# untitled_3.net
KiCad netlist of a schematic drawn in EAGLE
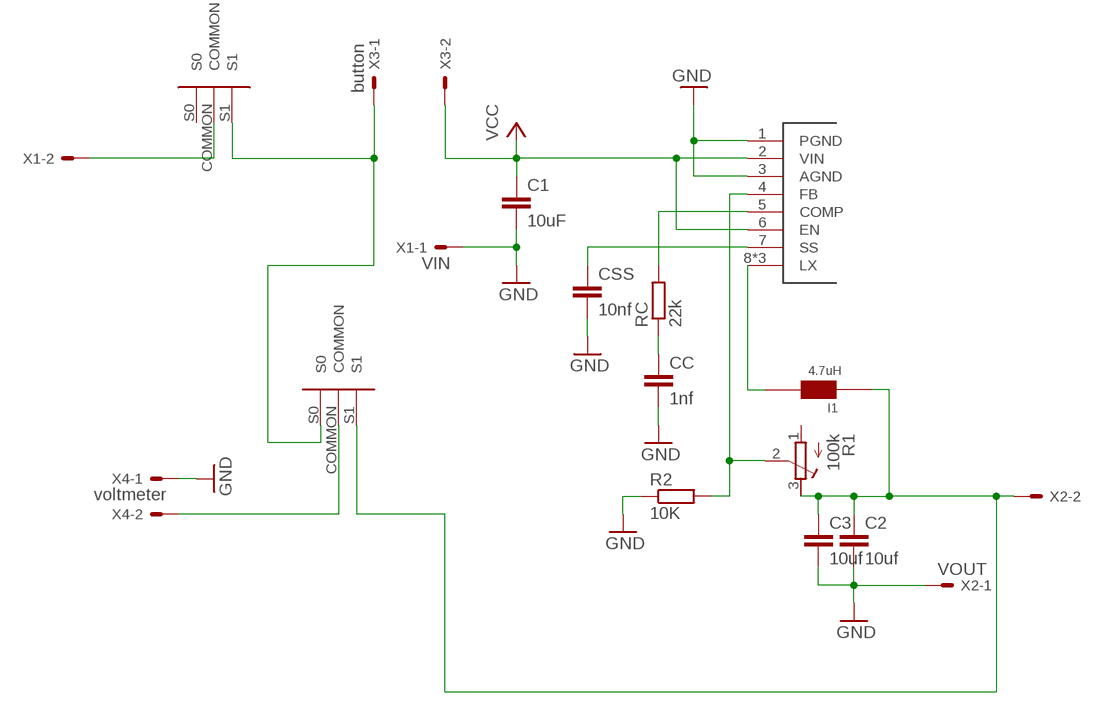
[diagram p0: schematic, sheet 1]

(export (version "E")
  (design (tool "Eeschema 10.0.6"))
  (components
    (comp (ref "C1")
      (value "10uF")
      (footprint "eagle-import:C0805K")
      (libsource (lib "eagle-import") (part "C-EUC0805K"))
    )
    (comp (ref "C2")
      (value "10uf")
      (footprint "eagle-import:C0805K")
      (libsource (lib "eagle-import") (part "C-EUC0805K"))
    )
    (comp (ref "C3")
      (value "10uf")
      (footprint "eagle-import:C0805K")
      (libsource (lib "eagle-import") (part "C-EUC0805K"))
    )
    (comp (ref "CC")
      (value "1nf")
      (footprint "eagle-import:C1206K")
      (libsource (lib "eagle-import") (part "C-EUC1206K"))
    )
    (comp (ref "CSS")
      (value "10nf")
      (footprint "eagle-import:C1206K")
      (libsource (lib "eagle-import") (part "C-EUC1206K"))
    )
    (comp (ref "I1")
      (value "4.7uH")
      (footprint "eagle-import:RH127")
      (libsource (lib "eagle-import") (part "RH127"))
    )
    (comp (ref "MASTER_ON")
      (value "SPDT_SLIDE_SWITCH_2_PITCH")
      (footprint "eagle-import:SPDT_SLIDE_SWITCH_2_PITCH")
      (libsource (lib "eagle-import") (part "SPDT_SLIDE_SWITCH_2_PITCH"))
    )
    (comp (ref "METER_SWITCH")
      (value "SPDT_SLIDE_SWITCH_2_PITCH")
      (footprint "eagle-import:SPDT_SLIDE_SWITCH_2_PITCH")
      (libsource (lib "eagle-import") (part "SPDT_SLIDE_SWITCH_2_PITCH"))
    )
    (comp (ref "R1")
      (value "100k")
      (footprint "eagle-import:RTRIM64W")
      (libsource (lib "eagle-import") (part "R-TRIMM64W"))
    )
    (comp (ref "R2")
      (value "10K")
      (footprint "eagle-import:R1206")
      (libsource (lib "eagle-import") (part "R-EU_R1206"))
    )
    (comp (ref "RC")
      (value "22k")
      (footprint "eagle-import:R1206")
      (libsource (lib "eagle-import") (part "R-EU_R1206"))
    )
    (comp (ref "U$3")
      (value "AOZ1051PI")
      (footprint "eagle-import:AOZ1051PI")
      (libsource (lib "eagle-import") (part "AOZ1051PI"))
    )
    (comp (ref "X1")
      (value "VIN")
      (footprint "eagle-import:XH2.54")
      (fields (field (name "MF") "MOLEX") (field (name "MPN") "22-23-2021"))
      (libsource (lib "eagle-import") (part "XH2.54"))
    )
    (comp (ref "X2")
      (value "VOUT")
      (footprint "eagle-import:XH2.54")
      (fields (field (name "MF") "MOLEX") (field (name "MPN") "22-23-2021"))
      (libsource (lib "eagle-import") (part "XH2.54"))
    )
    (comp (ref "X3")
      (value "button")
      (footprint "eagle-import:XH2.54")
      (fields (field (name "MF") "MOLEX") (field (name "MPN") "22-23-2021"))
      (libsource (lib "eagle-import") (part "XH2.54"))
    )
    (comp (ref "X4")
      (value "voltmeter")
      (footprint "eagle-import:XH2.54")
      (fields (field (name "MF") "MOLEX") (field (name "MPN") "22-23-2021"))
      (libsource (lib "eagle-import") (part "XH2.54"))
    )
  )
  (nets
    (net (code "1") (name "GND") (class "Default")
      (node (ref "C1") (pin "2") (pinfunction "2_2") (pintype "passive"))
      (node (ref "C2") (pin "2") (pinfunction "2_2") (pintype "passive"))
      (node (ref "C3") (pin "2") (pinfunction "2_2") (pintype "passive"))
      (node (ref "CC") (pin "2") (pinfunction "2_2") (pintype "passive"))
      (node (ref "CSS") (pin "2") (pinfunction "2_2") (pintype "passive"))
      (node (ref "R2") (pin "1") (pinfunction "1_1") (pintype "passive"))
      (node (ref "U$3") (pin "1") (pinfunction "PGND_1") (pintype "bidirectional"))
      (node (ref "U$3") (pin "3") (pinfunction "AGND_3") (pintype "bidirectional"))
      (node (ref "X1") (pin "1") (pinfunction "S_1") (pintype "passive"))
      (node (ref "X2") (pin "1") (pinfunction "S_1") (pintype "passive"))
      (node (ref "X4") (pin "1") (pinfunction "S_1") (pintype "passive"))
    )
    (net (code "2") (name "Net-(CC-Pad1)") (class "Default")
      (node (ref "CC") (pin "1") (pinfunction "1_1") (pintype "passive"))
      (node (ref "RC") (pin "1") (pinfunction "1_1") (pintype "passive"))
    )
    (net (code "3") (name "Net-(I1-PadP$1)") (class "Default")
      (node (ref "I1") (pin "P$1") (pinfunction "P$1_P$1") (pintype "bidirectional"))
      (node (ref "U$3") (pin "8") (pinfunction "LX_8") (pintype "bidirectional"))
      (node (ref "U$3") (pin "P$1") (pinfunction "LX_P$1") (pintype "bidirectional"))
      (node (ref "U$3") (pin "P$2") (pinfunction "LX_P$2") (pintype "bidirectional"))
    )
    (net (code "4") (name "Net-(R1-E)") (class "Default")
      (node (ref "C2") (pin "1") (pinfunction "1_1") (pintype "passive"))
      (node (ref "C3") (pin "1") (pinfunction "1_1") (pintype "passive"))
      (node (ref "I1") (pin "P$2") (pinfunction "P$2_P$2") (pintype "bidirectional"))
      (node (ref "METER_SWITCH") (pin "S1") (pinfunction "S1_S1") (pintype "bidirectional"))
      (node (ref "R1") (pin "3") (pinfunction "E_3") (pintype "passive"))
      (node (ref "X2") (pin "2") (pinfunction "S_2") (pintype "passive"))
    )
    (net (code "5") (name "Net-(R1-S)") (class "Default")
      (node (ref "R1") (pin "2") (pinfunction "S_2") (pintype "passive"))
      (node (ref "R2") (pin "2") (pinfunction "2_2") (pintype "passive"))
      (node (ref "U$3") (pin "4") (pinfunction "FB_4") (pintype "bidirectional"))
    )
    (net (code "6") (name "Net-(U$3-COMP)") (class "Default")
      (node (ref "RC") (pin "2") (pinfunction "2_2") (pintype "passive"))
      (node (ref "U$3") (pin "5") (pinfunction "COMP_5") (pintype "bidirectional"))
    )
    (net (code "7") (name "Net-(U$3-SS)") (class "Default")
      (node (ref "CSS") (pin "1") (pinfunction "1_1") (pintype "passive"))
      (node (ref "U$3") (pin "7") (pinfunction "SS_7") (pintype "bidirectional"))
    )
    (net (code "8") (name "Net-(X1B-S)") (class "Default")
      (node (ref "MASTER_ON") (pin "COMMON") (pinfunction "COMMON_COMMON") (pintype "bidirectional"))
      (node (ref "X1") (pin "2") (pinfunction "S_2") (pintype "passive"))
    )
    (net (code "9") (name "Net-(X3A-S)") (class "Default")
      (node (ref "MASTER_ON") (pin "S1") (pinfunction "S1_S1") (pintype "bidirectional"))
      (node (ref "METER_SWITCH") (pin "S0") (pinfunction "S0_S0") (pintype "bidirectional"))
      (node (ref "X3") (pin "1") (pinfunction "S_1") (pintype "passive"))
    )
    (net (code "10") (name "Net-(X4B-S)") (class "Default")
      (node (ref "METER_SWITCH") (pin "COMMON") (pinfunction "COMMON_COMMON") (pintype "bidirectional"))
      (node (ref "X4") (pin "2") (pinfunction "S_2") (pintype "passive"))
    )
    (net (code "11") (name "VCC") (class "Default")
      (node (ref "C1") (pin "1") (pinfunction "1_1") (pintype "passive"))
      (node (ref "U$3") (pin "2") (pinfunction "VIN_2") (pintype "bidirectional"))
      (node (ref "U$3") (pin "6") (pinfunction "EN_6") (pintype "bidirectional"))
      (node (ref "X3") (pin "2") (pinfunction "S_2") (pintype "passive"))
    )
    (net (code "12") (name "unconnected-(MASTER_ON-PadS0)") (class "Default")
      (node (ref "MASTER_ON") (pin "S0") (pinfunction "S0_S0") (pintype "bidirectional"))
    )
    (net (code "13") (name "unconnected-(R1-A-Pad1)") (class "Default")
      (node (ref "R1") (pin "1") (pinfunction "A_1") (pintype "passive"))
    )
  )
)
